# Voltage_Regulators.net
KiCad netlist of a schematic drawn in Altium Designer
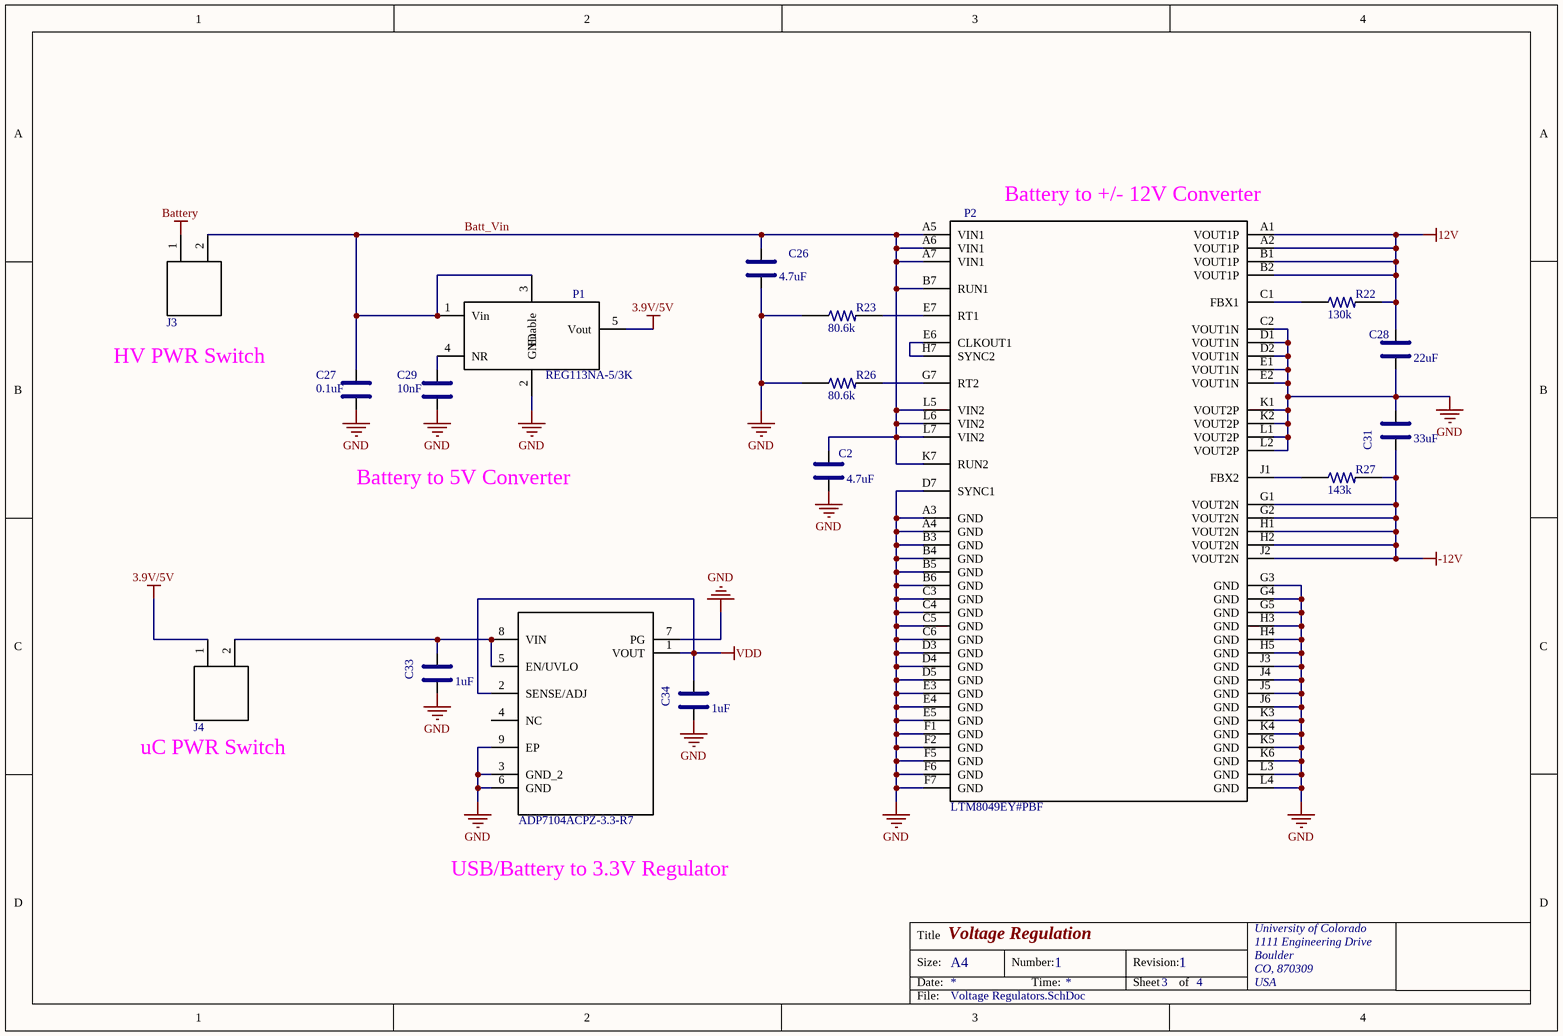
[diagram p0: Voltage Regulators.SchDoc]

(export (version "E")
  (design (tool "Eeschema 10.0.6"))
  (components
    (comp (ref "C2")
      (value "4.7uF")
      (footprint "C0402C102K9RACTU")
      (description "CAP CER 4.7UF 6.3V X5R 0402")
      (fields
        (field (name "MANUFACTURER") "Murata")
        (field (name "MANUFACTURER PART NUMBER") "GRM155R60J475ME47D‎")
      )
      (libsource (lib "Control_Board_Library") (part "GRM155R60J475"))
    )
    (comp (ref "C26")
      (value "4.7uF")
      (footprint "C0402C102K9RACTU")
      (description "CAP CER 4.7UF 6.3V X5R 0402")
      (fields
        (field (name "MANUFACTURER") "Murata")
        (field (name "MANUFACTURER PART NUMBER") "GRM155R60J475ME47D‎")
      )
      (libsource (lib "Control_Board_Library") (part "GRM155R60J475"))
    )
    (comp (ref "C27")
      (value "0.1uF")
      (footprint "CL03A104KA3NNNC")
      (description "CAP CER 0.1UF 25V X5R 0201")
      (fields
        (field (name "MANUFACTURER") "Samsung")
        (field (name "MANUFACTURER PART NUMBER") "CL03A104KA3NNNC")
      )
      (libsource (lib "Sensing PEANO_Library") (part "CL03A104KA3NNNC"))
    )
    (comp (ref "C28")
      (value "22uF")
      (footprint "CL21A226MAQNNNE")
      (description "CAP CER 22UF 25V X5R 0805")
      (fields
        (field (name "MANUFACTURER") "Samsung")
        (field (name "MANUFACTURER PART NUMBER") "CL21A226MAQNNNE")
      )
      (libsource (lib "Sensing PEANO_Library") (part "CL21A226MAQNNNE"))
    )
    (comp (ref "C29")
      (value "10nF")
      (footprint "CL03A104KA3NNNC")
      (description "CAP CER 0.1UF 25V X5R 0201")
      (fields
        (field (name "MANUFACTURER") "Samsung")
        (field (name "MANUFACTURER PART NUMBER") "CL03A104KA3NNNC")
      )
      (libsource (lib "Sensing PEANO_Library") (part "CL03A104KA3NNNC"))
    )
    (comp (ref "C31")
      (value "33uF")
      (footprint "GRM31CR61E476ME44L")
      (description "CAP CER 33UF 25V JB 1206")
      (fields
        (field (name "MANUFACTURER") "TDK Corporation")
        (field (name "MANUFACTURER PART NUMBER") "C3216JB1E336M160AC")
      )
      (libsource (lib "Control_Board_Library") (part "C3216JB1E336M160AC"))
    )
    (comp (ref "C33")
      (value "1uF")
      (footprint "GRM033R60J105MEA2D")
      (description "CAP CER 1UF 6.3V X5R 0201")
      (fields
        (field (name "MANUFACTURER") "Murata")
        (field (name "MANUFACTURER PART NUMBER") "GRM033R60J105MEA2D")
      )
      (libsource (lib "Control_Board_Library") (part "GRM033R60J105MEA2D"))
    )
    (comp (ref "C34")
      (value "1uF")
      (footprint "GRM033R60J105MEA2D")
      (description "CAP CER 1UF 6.3V X5R 0201")
      (fields
        (field (name "MANUFACTURER") "Murata")
        (field (name "MANUFACTURER PART NUMBER") "GRM033R60J105MEA2D")
      )
      (libsource (lib "Control_Board_Library") (part "GRM033R60J105MEA2D"))
    )
    (comp (ref "J3")
      (value "BM02B-SRSS-TBT")
      (footprint "BM02B-SRSS-TBT")
      (description "CONN WIRE HDR 2POS 1MM STSMD")
      (fields (field (name "MANUFACTURER") "JST") (field (name "DIGIKEY PART NUMBER") "455-2955-1-ND"))
      (libsource (lib "Sensing PEANO_Library") (part "BM02B-SRSS-TBT"))
    )
    (comp (ref "J4")
      (value "BM02B-SRSS-TBT")
      (footprint "BM02B-SRSS-TBT")
      (description "CONN WIRE HDR 2POS 1MM STSMD")
      (fields (field (name "MANUFACTURER") "JST") (field (name "DIGIKEY PART NUMBER") "455-2955-1-ND"))
      (libsource (lib "Sensing PEANO_Library") (part "BM02B-SRSS-TBT"))
    )
    (comp (ref "P1")
      (value "REG113NA-5/3K")
      (footprint "REG113NA-5/3K")
      (description "LDO Voltage Regulators DMOS 400mA Regulator Low-Dropout")
      (fields (field (name "MANUFACTURER") "LT"))
      (libsource (lib "Control_Board_Library") (part "REG113NA-5/3K"))
    )
    (comp (ref "P2")
      (value "LTM8049EY#PBF")
      (footprint "LTM8049EY#PBF")
      (description "DC DC CONVERTER +/-2.5 TO +/-24V")
      (fields
        (field (name "DIGIKEY PART NUMBER") "LTM8049EY#PBF-ND")
        (field (name "MANUFACTURER") "Linear Technology")
      )
      (libsource (lib "Sensing PEANO_Library") (part "LTM8049EY#PBF"))
    )
    (comp (ref "P3")
      (value "ADP7104ACPZ-3.3-R7")
      (footprint "ADP7104ARDZ-3.3")
      (description "IC REG LINEAR 3.3V 500MA 8LFCSP")
      (fields
        (field (name "MANUFACTURER") "Analog Devices")
        (field (name "DIGIKEY PART NUMBER") "ADP7104ACPZ-3.3-R7DKR-ND")
      )
      (libsource (lib "Control_Board_Library") (part "ADP7104ACPZ-3.3-R7"))
    )
    (comp (ref "R22")
      (value "130k")
      (footprint "RC0201FR-07130KL")
      (description "RES SMD 130K OHM 1% 1/20W 0201")
      (fields
        (field (name "MANUFACTURER") "Yageo")
        (field (name "MANUFACTURER PART NUMBER") "RC0201FR-07130KL")
      )
      (libsource (lib "Sensing PEANO_Library") (part "RC0201FR-07130KL"))
    )
    (comp (ref "R23")
      (value "80.6k")
      (footprint "RC0201FR-0780K6L")
      (description "RES SMD 80.6K OHM 1% 1/20W 0201")
      (fields
        (field (name "MANUFACTURER") "Yageo")
        (field (name "MANUFACTURER PART NUMBER") "RC0201FR-0780K6L")
      )
      (libsource (lib "Sensing PEANO_Library") (part "RC0201FR-0780K6L"))
    )
    (comp (ref "R26")
      (value "80.6k")
      (footprint "RC0201FR-0780K6L")
      (description "RES SMD 80.6K OHM 1% 1/20W 0201")
      (fields
        (field (name "MANUFACTURER") "Yageo")
        (field (name "MANUFACTURER PART NUMBER") "RC0201FR-0780K6L")
      )
      (libsource (lib "Sensing PEANO_Library") (part "RC0201FR-0780K6L"))
    )
    (comp (ref "R27")
      (value "143k")
      (footprint "RC0201FR-07143KL")
      (description "RES SMD 143K OHM 1% 1/20W 0201")
      (fields
        (field (name "MANUFACTURER") "Yageo")
        (field (name "MANUFACTURER PART NUMBER") "RC0201FR-07143KL")
      )
      (libsource (lib "Sensing PEANO_Library") (part "RC0201FR-07143KL"))
    )
  )
  (nets
    (net (code "1") (name "-12V") (class "Default")
      (node (ref "C31") (pin "2") (pinfunction "2_2") (pintype "passive"))
      (node (ref "P2") (pin "G1") (pinfunction "VOUT2N_G1") (pintype "passive"))
      (node (ref "P2") (pin "G2") (pinfunction "VOUT2N_G2") (pintype "passive"))
      (node (ref "P2") (pin "H1") (pinfunction "VOUT2N_H1") (pintype "passive"))
      (node (ref "P2") (pin "H2") (pinfunction "VOUT2N_H2") (pintype "passive"))
      (node (ref "P2") (pin "J2") (pinfunction "VOUT2N_J2") (pintype "passive"))
      (node (ref "R27") (pin "1") (pinfunction "1_1") (pintype "passive"))
    )
    (net (code "2") (name "/Batt_Vin") (class "Default")
      (node (ref "C2") (pin "1") (pinfunction "1_1") (pintype "passive"))
      (node (ref "C26") (pin "1") (pinfunction "1_1") (pintype "passive"))
      (node (ref "C27") (pin "2") (pinfunction "2_2") (pintype "passive"))
      (node (ref "J3") (pin "2") (pinfunction "2_2") (pintype "passive"))
      (node (ref "P1") (pin "1") (pinfunction "Vin_1") (pintype "passive"))
      (node (ref "P1") (pin "3") (pinfunction "Enable_3") (pintype "passive"))
      (node (ref "P2") (pin "A5") (pinfunction "VIN1_A5") (pintype "passive"))
      (node (ref "P2") (pin "A6") (pinfunction "VIN1_A6") (pintype "passive"))
      (node (ref "P2") (pin "A7") (pinfunction "VIN1_A7") (pintype "passive"))
      (node (ref "P2") (pin "B7") (pinfunction "RUN1_B7") (pintype "passive"))
      (node (ref "P2") (pin "K7") (pinfunction "RUN2_K7") (pintype "passive"))
      (node (ref "P2") (pin "L5") (pinfunction "VIN2_L5") (pintype "passive"))
      (node (ref "P2") (pin "L6") (pinfunction "VIN2_L6") (pintype "passive"))
      (node (ref "P2") (pin "L7") (pinfunction "VIN2_L7") (pintype "passive"))
    )
    (net (code "3") (name "3.9V{slash}5V") (class "Default")
      (node (ref "J4") (pin "1") (pinfunction "1_1") (pintype "passive"))
      (node (ref "P1") (pin "5") (pinfunction "Vout_5") (pintype "passive"))
    )
    (net (code "4") (name "12V") (class "Default")
      (node (ref "C28") (pin "1") (pinfunction "1_1") (pintype "passive"))
      (node (ref "P2") (pin "A1") (pinfunction "VOUT1P_A1") (pintype "passive"))
      (node (ref "P2") (pin "A2") (pinfunction "VOUT1P_A2") (pintype "passive"))
      (node (ref "P2") (pin "B1") (pinfunction "VOUT1P_B1") (pintype "passive"))
      (node (ref "P2") (pin "B2") (pinfunction "VOUT1P_B2") (pintype "passive"))
      (node (ref "R22") (pin "1") (pinfunction "1_1") (pintype "passive"))
    )
    (net (code "5") (name "Battery") (class "Default")
      (node (ref "J3") (pin "1") (pinfunction "1_1") (pintype "passive"))
    )
    (net (code "6") (name "GND") (class "Default")
      (node (ref "C2") (pin "2") (pinfunction "2_2") (pintype "passive"))
      (node (ref "C26") (pin "2") (pinfunction "2_2") (pintype "passive"))
      (node (ref "C27") (pin "1") (pinfunction "1_1") (pintype "passive"))
      (node (ref "C28") (pin "2") (pinfunction "2_2") (pintype "passive"))
      (node (ref "C29") (pin "2") (pinfunction "2_2") (pintype "passive"))
      (node (ref "C31") (pin "1") (pinfunction "1_1") (pintype "passive"))
      (node (ref "C33") (pin "2") (pinfunction "2_2") (pintype "passive"))
      (node (ref "C34") (pin "2") (pinfunction "2_2") (pintype "passive"))
      (node (ref "P1") (pin "2") (pinfunction "GND_2") (pintype "passive"))
      (node (ref "P2") (pin "A3") (pinfunction "GND_A3") (pintype "passive"))
      (node (ref "P2") (pin "A4") (pinfunction "GND_A4") (pintype "passive"))
      (node (ref "P2") (pin "B3") (pinfunction "GND_B3") (pintype "passive"))
      (node (ref "P2") (pin "B4") (pinfunction "GND_B4") (pintype "passive"))
      (node (ref "P2") (pin "B5") (pinfunction "GND_B5") (pintype "passive"))
      (node (ref "P2") (pin "B6") (pinfunction "GND_B6") (pintype "passive"))
      (node (ref "P2") (pin "C2") (pinfunction "VOUT1N_C2") (pintype "passive"))
      (node (ref "P2") (pin "C3") (pinfunction "GND_C3") (pintype "passive"))
      (node (ref "P2") (pin "C4") (pinfunction "GND_C4") (pintype "passive"))
      (node (ref "P2") (pin "C5") (pinfunction "GND_C5") (pintype "passive"))
      (node (ref "P2") (pin "C6") (pinfunction "GND_C6") (pintype "passive"))
      (node (ref "P2") (pin "D1") (pinfunction "VOUT1N_D1") (pintype "passive"))
      (node (ref "P2") (pin "D2") (pinfunction "VOUT1N_D2") (pintype "passive"))
      (node (ref "P2") (pin "D3") (pinfunction "GND_D3") (pintype "passive"))
      (node (ref "P2") (pin "D4") (pinfunction "GND_D4") (pintype "passive"))
      (node (ref "P2") (pin "D5") (pinfunction "GND_D5") (pintype "passive"))
      (node (ref "P2") (pin "D7") (pinfunction "SYNC1_D7") (pintype "passive"))
      (node (ref "P2") (pin "E1") (pinfunction "VOUT1N_E1") (pintype "passive"))
      (node (ref "P2") (pin "E2") (pinfunction "VOUT1N_E2") (pintype "passive"))
      (node (ref "P2") (pin "E3") (pinfunction "GND_E3") (pintype "passive"))
      (node (ref "P2") (pin "E4") (pinfunction "GND_E4") (pintype "passive"))
      (node (ref "P2") (pin "E5") (pinfunction "GND_E5") (pintype "passive"))
      (node (ref "P2") (pin "F1") (pinfunction "GND_F1") (pintype "passive"))
      (node (ref "P2") (pin "F2") (pinfunction "GND_F2") (pintype "passive"))
      (node (ref "P2") (pin "F5") (pinfunction "GND_F5") (pintype "passive"))
      (node (ref "P2") (pin "F6") (pinfunction "GND_F6") (pintype "passive"))
      (node (ref "P2") (pin "F7") (pinfunction "GND_F7") (pintype "passive"))
      (node (ref "P2") (pin "G3") (pinfunction "GND_G3") (pintype "passive"))
      (node (ref "P2") (pin "G4") (pinfunction "GND_G4") (pintype "passive"))
      (node (ref "P2") (pin "G5") (pinfunction "GND_G5") (pintype "passive"))
      (node (ref "P2") (pin "H3") (pinfunction "GND_H3") (pintype "passive"))
      (node (ref "P2") (pin "H4") (pinfunction "GND_H4") (pintype "passive"))
      (node (ref "P2") (pin "H5") (pinfunction "GND_H5") (pintype "passive"))
      (node (ref "P2") (pin "J3") (pinfunction "GND_J3") (pintype "passive"))
      (node (ref "P2") (pin "J4") (pinfunction "GND_J4") (pintype "passive"))
      (node (ref "P2") (pin "J5") (pinfunction "GND_J5") (pintype "passive"))
      (node (ref "P2") (pin "J6") (pinfunction "GND_J6") (pintype "passive"))
      (node (ref "P2") (pin "K1") (pinfunction "VOUT2P_K1") (pintype "passive"))
      (node (ref "P2") (pin "K2") (pinfunction "VOUT2P_K2") (pintype "passive"))
      (node (ref "P2") (pin "K3") (pinfunction "GND_K3") (pintype "passive"))
      (node (ref "P2") (pin "K4") (pinfunction "GND_K4") (pintype "passive"))
      (node (ref "P2") (pin "K5") (pinfunction "GND_K5") (pintype "passive"))
      (node (ref "P2") (pin "K6") (pinfunction "GND_K6") (pintype "passive"))
      (node (ref "P2") (pin "L1") (pinfunction "VOUT2P_L1") (pintype "passive"))
      (node (ref "P2") (pin "L2") (pinfunction "VOUT2P_L2") (pintype "passive"))
      (node (ref "P2") (pin "L3") (pinfunction "GND_L3") (pintype "passive"))
      (node (ref "P2") (pin "L4") (pinfunction "GND_L4") (pintype "passive"))
      (node (ref "P3") (pin "3") (pinfunction "GND_2_3") (pintype "passive"))
      (node (ref "P3") (pin "6") (pinfunction "GND_6") (pintype "passive"))
      (node (ref "P3") (pin "7") (pinfunction "PG_7") (pintype "passive"))
      (node (ref "P3") (pin "9") (pinfunction "EP_9") (pintype "passive"))
      (node (ref "R23") (pin "2") (pinfunction "2_2") (pintype "passive"))
      (node (ref "R26") (pin "2") (pinfunction "2_2") (pintype "passive"))
    )
    (net (code "7") (name "Net-(P1-NR)") (class "Default")
      (node (ref "C29") (pin "1") (pinfunction "1_1") (pintype "passive"))
      (node (ref "P1") (pin "4") (pinfunction "NR_4") (pintype "passive"))
    )
    (net (code "8") (name "Net-(P2-CLKOUT1)") (class "Default")
      (node (ref "P2") (pin "E6") (pinfunction "CLKOUT1_E6") (pintype "passive"))
      (node (ref "P2") (pin "H7") (pinfunction "SYNC2_H7") (pintype "passive"))
    )
    (net (code "9") (name "Net-(P2-FBX1)") (class "Default")
      (node (ref "P2") (pin "C1") (pinfunction "FBX1_C1") (pintype "passive"))
      (node (ref "R22") (pin "2") (pinfunction "2_2") (pintype "passive"))
    )
    (net (code "10") (name "Net-(P2-FBX2)") (class "Default")
      (node (ref "P2") (pin "J1") (pinfunction "FBX2_J1") (pintype "passive"))
      (node (ref "R27") (pin "2") (pinfunction "2_2") (pintype "passive"))
    )
    (net (code "11") (name "Net-(P2-RT1)") (class "Default")
      (node (ref "P2") (pin "E7") (pinfunction "RT1_E7") (pintype "passive"))
      (node (ref "R23") (pin "1") (pinfunction "1_1") (pintype "passive"))
    )
    (net (code "12") (name "Net-(P2-RT2)") (class "Default")
      (node (ref "P2") (pin "G7") (pinfunction "RT2_G7") (pintype "passive"))
      (node (ref "R26") (pin "1") (pinfunction "1_1") (pintype "passive"))
    )
    (net (code "13") (name "Net-(P3-EN{slash}UVLO)") (class "Default")
      (node (ref "C33") (pin "1") (pinfunction "1_1") (pintype "passive"))
      (node (ref "J4") (pin "2") (pinfunction "2_2") (pintype "passive"))
      (node (ref "P3") (pin "5") (pinfunction "EN/UVLO_5") (pintype "passive"))
      (node (ref "P3") (pin "8") (pinfunction "VIN_8") (pintype "passive"))
    )
    (net (code "14") (name "VDD") (class "Default")
      (node (ref "C34") (pin "1") (pinfunction "1_1") (pintype "passive"))
      (node (ref "P3") (pin "1") (pinfunction "VOUT_1") (pintype "passive"))
      (node (ref "P3") (pin "2") (pinfunction "SENSE/ADJ_2") (pintype "passive"))
    )
    (net (code "15") (name "unconnected-(P3-NC-Pad4)") (class "Default")
      (node (ref "P3") (pin "4") (pinfunction "NC_4") (pintype "passive"))
    )
  )
)
